# macse.net
KiCad netlist of a schematic drawn in EAGLE
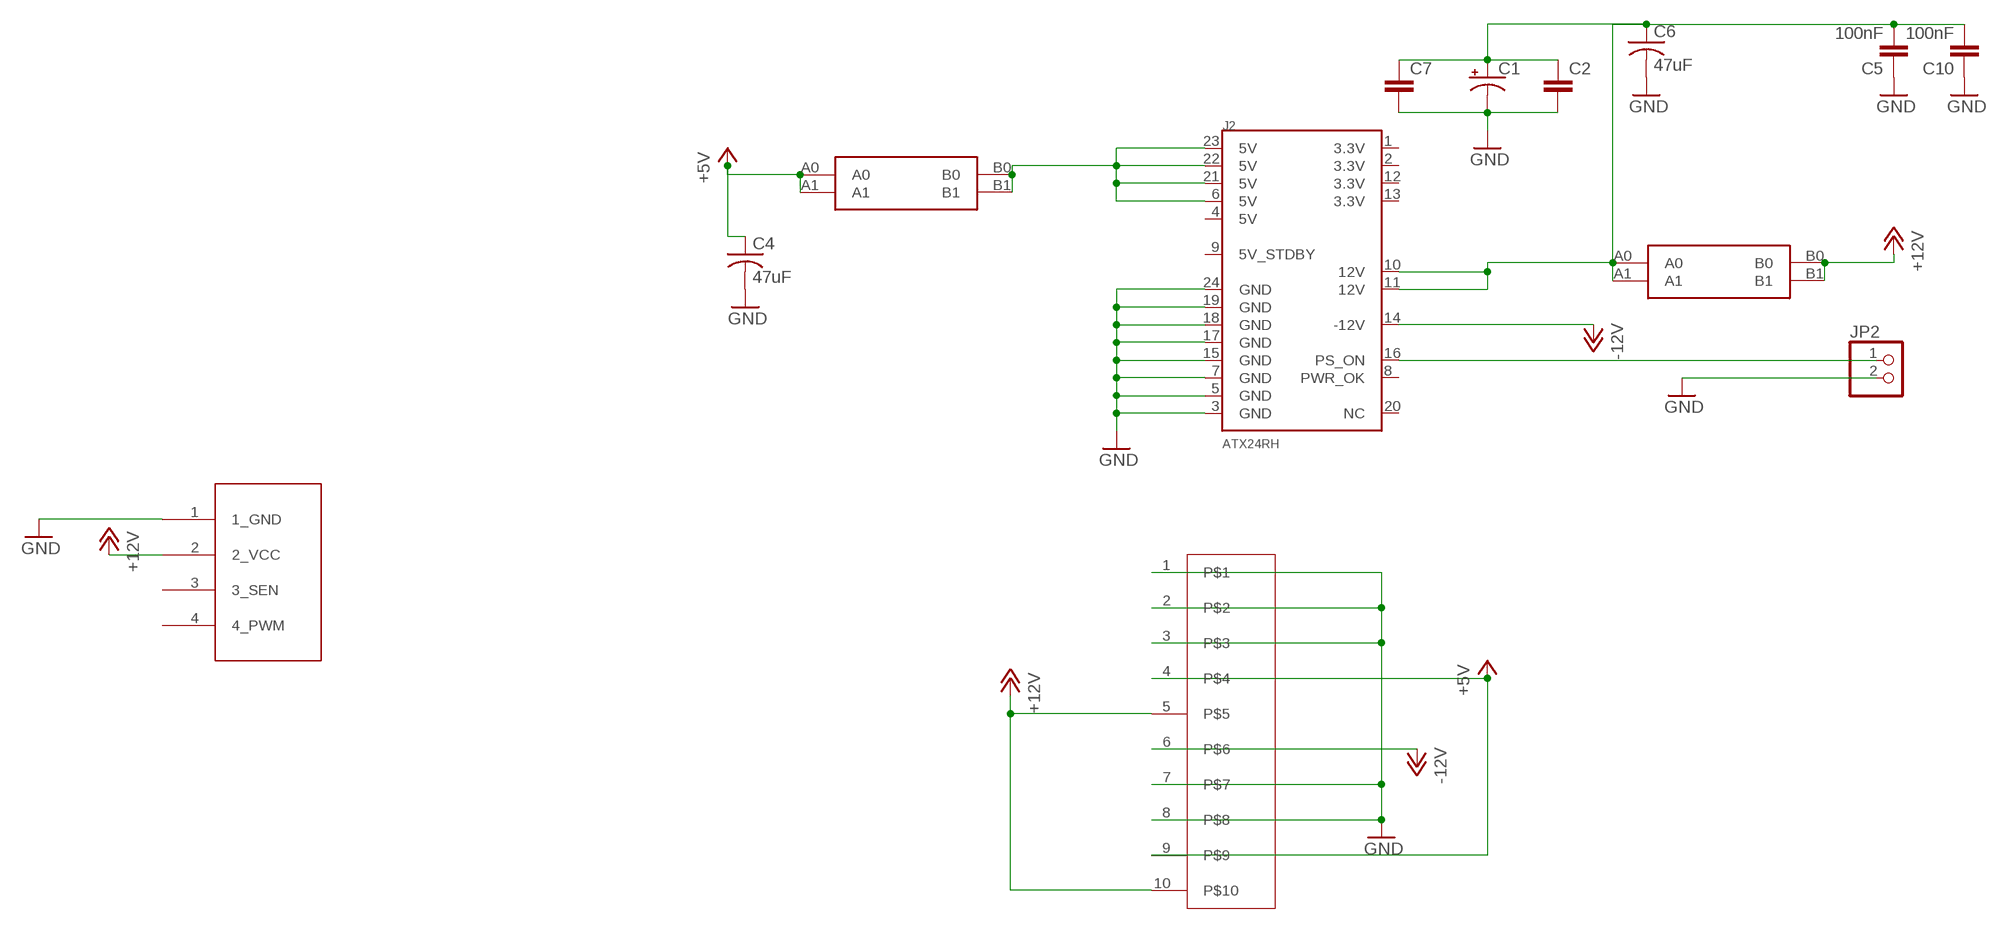
[diagram p0: schematic, sheet 1]

(export (version "E")
  (design (tool "Eeschema 10.0.6"))
  (components
    (comp (ref "C1")
      (value "CPOL-USE3.5-8")
      (footprint "eagle-import:E3,5-8")
      (libsource (lib "eagle-import") (part "CPOL-USE3.5-8"))
    )
    (comp (ref "C2")
      (value "C5/2.5")
      (footprint "eagle-import:C5B2.5")
      (libsource (lib "eagle-import") (part "C5/2.5"))
    )
    (comp (ref "C4")
      (value "47uF")
      (footprint "eagle-import:C1210")
      (libsource (lib "eagle-import") (part "C-USC1210"))
    )
    (comp (ref "C5")
      (value "100nF")
      (footprint "eagle-import:0805@1")
      (libsource (lib "eagle-import") (part "CAP0805"))
    )
    (comp (ref "C6")
      (value "47uF")
      (footprint "eagle-import:C1210")
      (libsource (lib "eagle-import") (part "C-USC1210"))
    )
    (comp (ref "C7")
      (value "C5/2.5")
      (footprint "eagle-import:C5B2.5")
      (libsource (lib "eagle-import") (part "C5/2.5"))
    )
    (comp (ref "C10")
      (value "100nF")
      (footprint "eagle-import:0805@1")
      (libsource (lib "eagle-import") (part "CAP0805"))
    )
    (comp (ref "J2")
      (value "ATX24RH")
      (footprint "eagle-import:ATX24_RIGHT_ANGLE")
      (libsource (lib "eagle-import") (part "ATX24RH"))
    )
    (comp (ref "JP2")
      (value "PINHD-1X2/90")
      (footprint "eagle-import:1X02_90")
      (libsource (lib "eagle-import") (part "PINHD-1X2/90"))
    )
    (comp (ref "JP3")
      (value "4PIN_FAN")
      (footprint "eagle-import:1X04")
      (libsource (lib "eagle-import") (part "4PIN_FAN"))
    )
    (comp (ref "U$1")
      (value "MACSE")
      (footprint "eagle-import:MACSE_10P_STRAIGHT")
      (libsource (lib "eagle-import") (part "MACSE"))
    )
    (comp (ref "U$2")
      (value "CAR_FUSE_HOLDER3IN1")
      (footprint "eagle-import:FUSE_HOLDER_3IN1")
      (libsource (lib "eagle-import") (part "CAR_FUSE_HOLDER3IN1"))
    )
    (comp (ref "U$8")
      (value "CAR_FUSE_HOLDER3IN1")
      (footprint "eagle-import:FUSE_HOLDER_3IN1")
      (libsource (lib "eagle-import") (part "CAR_FUSE_HOLDER3IN1"))
    )
  )
  (nets
    (net (code "1") (name "+5V") (class "Default")
      (node (ref "C4") (pin "1") (pinfunction "1_1") (pintype "passive"))
      (node (ref "U$1") (pin "4") (pinfunction "P$4_4") (pintype "bidirectional"))
      (node (ref "U$1") (pin "9") (pinfunction "P$9_9") (pintype "bidirectional"))
      (node (ref "U$8") (pin "A0") (pinfunction "A0_A0") (pintype "bidirectional"))
      (node (ref "U$8") (pin "A1") (pinfunction "A1_A1") (pintype "bidirectional"))
    )
    (net (code "2") (name "+12V") (class "Default")
      (node (ref "JP3") (pin "2") (pinfunction "2_VCC_2") (pintype "passive"))
      (node (ref "U$1") (pin "10") (pinfunction "P$10_10") (pintype "bidirectional"))
      (node (ref "U$1") (pin "5") (pinfunction "P$5_5") (pintype "bidirectional"))
      (node (ref "U$2") (pin "B0") (pinfunction "B0_B0") (pintype "bidirectional"))
      (node (ref "U$2") (pin "B1") (pinfunction "B1_B1") (pintype "bidirectional"))
    )
    (net (code "3") (name "-12V") (class "Default")
      (node (ref "J2") (pin "14") (pinfunction "-12V_14") (pintype "bidirectional"))
      (node (ref "U$1") (pin "6") (pinfunction "P$6_6") (pintype "bidirectional"))
    )
    (net (code "4") (name "GND") (class "Default")
      (node (ref "C1") (pin "-") (pinfunction "-_-") (pintype "passive"))
      (node (ref "C10") (pin "1") (pinfunction "1_1") (pintype "passive"))
      (node (ref "C2") (pin "2") (pinfunction "2_2") (pintype "passive"))
      (node (ref "C4") (pin "2") (pinfunction "2_2") (pintype "passive"))
      (node (ref "C5") (pin "1") (pinfunction "1_1") (pintype "passive"))
      (node (ref "C6") (pin "2") (pinfunction "2_2") (pintype "passive"))
      (node (ref "C7") (pin "2") (pinfunction "2_2") (pintype "passive"))
      (node (ref "J2") (pin "15") (pinfunction "GND_15") (pintype "bidirectional"))
      (node (ref "J2") (pin "17") (pinfunction "GND_17") (pintype "bidirectional"))
      (node (ref "J2") (pin "18") (pinfunction "GND_18") (pintype "bidirectional"))
      (node (ref "J2") (pin "19") (pinfunction "GND_19") (pintype "bidirectional"))
      (node (ref "J2") (pin "24") (pinfunction "GND_24") (pintype "bidirectional"))
      (node (ref "J2") (pin "3") (pinfunction "GND_3") (pintype "bidirectional"))
      (node (ref "J2") (pin "5") (pinfunction "GND_5") (pintype "bidirectional"))
      (node (ref "J2") (pin "7") (pinfunction "GND_7") (pintype "bidirectional"))
      (node (ref "JP2") (pin "2") (pinfunction "2_2") (pintype "passive"))
      (node (ref "JP3") (pin "1") (pinfunction "1_GND_1") (pintype "passive"))
      (node (ref "U$1") (pin "1") (pinfunction "P$1_1") (pintype "bidirectional"))
      (node (ref "U$1") (pin "2") (pinfunction "P$2_2") (pintype "bidirectional"))
      (node (ref "U$1") (pin "3") (pinfunction "P$3_3") (pintype "bidirectional"))
      (node (ref "U$1") (pin "7") (pinfunction "P$7_7") (pintype "bidirectional"))
      (node (ref "U$1") (pin "8") (pinfunction "P$8_8") (pintype "bidirectional"))
    )
    (net (code "5") (name "Net-(C1-Pad+)") (class "Default")
      (node (ref "C1") (pin "+") (pinfunction "+_+") (pintype "passive"))
      (node (ref "C10") (pin "2") (pinfunction "2_2") (pintype "passive"))
      (node (ref "C2") (pin "1") (pinfunction "1_1") (pintype "passive"))
      (node (ref "C5") (pin "2") (pinfunction "2_2") (pintype "passive"))
      (node (ref "C6") (pin "1") (pinfunction "1_1") (pintype "passive"))
      (node (ref "C7") (pin "1") (pinfunction "1_1") (pintype "passive"))
      (node (ref "J2") (pin "10") (pinfunction "12V_10") (pintype "bidirectional"))
      (node (ref "J2") (pin "11") (pinfunction "12V_11") (pintype "bidirectional"))
      (node (ref "U$2") (pin "A0") (pinfunction "A0_A0") (pintype "bidirectional"))
      (node (ref "U$2") (pin "A1") (pinfunction "A1_A1") (pintype "bidirectional"))
    )
    (net (code "6") (name "Net-(J2-5V-Pad21)") (class "Default")
      (node (ref "J2") (pin "21") (pinfunction "5V_21") (pintype "bidirectional"))
      (node (ref "J2") (pin "22") (pinfunction "5V_22") (pintype "bidirectional"))
      (node (ref "J2") (pin "23") (pinfunction "5V_23") (pintype "bidirectional"))
      (node (ref "J2") (pin "6") (pinfunction "5V_6") (pintype "bidirectional"))
      (node (ref "U$8") (pin "B0") (pinfunction "B0_B0") (pintype "bidirectional"))
      (node (ref "U$8") (pin "B1") (pinfunction "B1_B1") (pintype "bidirectional"))
    )
    (net (code "7") (name "Net-(J2-PS_ON)") (class "Default")
      (node (ref "J2") (pin "16") (pinfunction "PS_ON_16") (pintype "bidirectional"))
      (node (ref "JP2") (pin "1") (pinfunction "1_1") (pintype "passive"))
    )
    (net (code "8") (name "unconnected-(J2-3.3V-Pad1)") (class "Default")
      (node (ref "J2") (pin "1") (pinfunction "3.3V_1") (pintype "bidirectional"))
    )
    (net (code "9") (name "unconnected-(J2-3.3V-Pad2)") (class "Default")
      (node (ref "J2") (pin "2") (pinfunction "3.3V_2") (pintype "bidirectional"))
    )
    (net (code "10") (name "unconnected-(J2-3.3V-Pad12)") (class "Default")
      (node (ref "J2") (pin "12") (pinfunction "3.3V_12") (pintype "bidirectional"))
    )
    (net (code "11") (name "unconnected-(J2-3.3V-Pad13)") (class "Default")
      (node (ref "J2") (pin "13") (pinfunction "3.3V_13") (pintype "bidirectional"))
    )
    (net (code "12") (name "unconnected-(J2-5V-Pad4)") (class "Default")
      (node (ref "J2") (pin "4") (pinfunction "5V_4") (pintype "bidirectional"))
    )
    (net (code "13") (name "unconnected-(J2-5V_STDBY-Pad9)") (class "Default")
      (node (ref "J2") (pin "9") (pinfunction "5V_STDBY_9") (pintype "bidirectional"))
    )
    (net (code "14") (name "unconnected-(J2-NC-Pad20)") (class "Default")
      (node (ref "J2") (pin "20") (pinfunction "NC_20") (pintype "bidirectional"))
    )
    (net (code "15") (name "unconnected-(J2-PWR_OK-Pad8)") (class "Default")
      (node (ref "J2") (pin "8") (pinfunction "PWR_OK_8") (pintype "bidirectional"))
    )
    (net (code "16") (name "unconnected-(JP3-3_SEN-Pad3)") (class "Default")
      (node (ref "JP3") (pin "3") (pinfunction "3_SEN_3") (pintype "passive"))
    )
    (net (code "17") (name "unconnected-(JP3-4_PWM-Pad4)") (class "Default")
      (node (ref "JP3") (pin "4") (pinfunction "4_PWM_4") (pintype "passive"))
    )
  )
)
